# adc_reference.net
KiCad netlist of a schematic drawn in Altium Designer
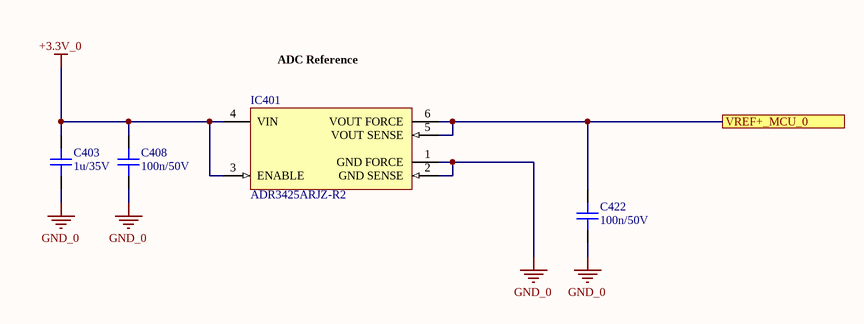
[diagram p0: adc_reference.SchDoc]

(export (version "E")
  (design (tool "Eeschema 10.0.6"))
  (components
    (comp (ref "C403")
      (value "1u/35V")
      (footprint "CAPC1608X08N")
      (description "MLCC")
      (fields (field (name "PART NUMBER") "gen_C_ceramic_1u_35V_X7R_0603"))
      (libsource (lib "OE750") (part "C"))
    )
    (comp (ref "C408")
      (value "100n/50V")
      (footprint "CAPC1608X08N")
      (description "MLCC")
      (fields (field (name "PART NUMBER") "gen_C_ceramic_100n_50V_X7R_0603"))
      (libsource (lib "OE750") (part "C"))
    )
    (comp (ref "C422")
      (value "100n/50V")
      (footprint "CAPC1608X08N")
      (description "MLCC")
      (fields (field (name "PART NUMBER") "gen_C_ceramic_100n_50V_X7R_0603"))
      (libsource (lib "OE750") (part "C"))
    )
    (comp (ref "IC401")
      (value "ADR3425ARJZ-R2")
      (footprint "ADI-RJ-6_N")
      (fields (field (name "MANUFACTURER") "Analog Devices"))
      (libsource (lib "Altium Content Vault") (part "ADI-ADR34xx-RJ-6"))
    )
  )
  (nets
    (net (code "1") (name "+3.3V_0") (class "Default")
      (node (ref "C403") (pin "1") (pinfunction "1_1") (pintype "passive"))
      (node (ref "C408") (pin "1") (pinfunction "1_1") (pintype "passive"))
      (node (ref "IC401") (pin "3") (pinfunction "ENABLE_3") (pintype "input"))
      (node (ref "IC401") (pin "4") (pinfunction "VIN_4") (pintype "power_in"))
    )
    (net (code "2") (name "/VREF+_MCU_0") (class "Default")
      (node (ref "C422") (pin "1") (pinfunction "1_1") (pintype "passive"))
      (node (ref "IC401") (pin "5") (pinfunction "VOUT_SENSE_5") (pintype "input"))
      (node (ref "IC401") (pin "6") (pinfunction "VOUT_FORCE_6") (pintype "power_in"))
    )
    (net (code "3") (name "GND_0") (class "Default")
      (node (ref "C403") (pin "2") (pinfunction "2_2") (pintype "passive"))
      (node (ref "C408") (pin "2") (pinfunction "2_2") (pintype "passive"))
      (node (ref "C422") (pin "2") (pinfunction "2_2") (pintype "passive"))
      (node (ref "IC401") (pin "1") (pinfunction "GND_FORCE_1") (pintype "power_in"))
      (node (ref "IC401") (pin "2") (pinfunction "GND_SENSE_2") (pintype "input"))
    )
  )
)
